# lp_basic.net
KiCad netlist of a schematic drawn in EAGLE
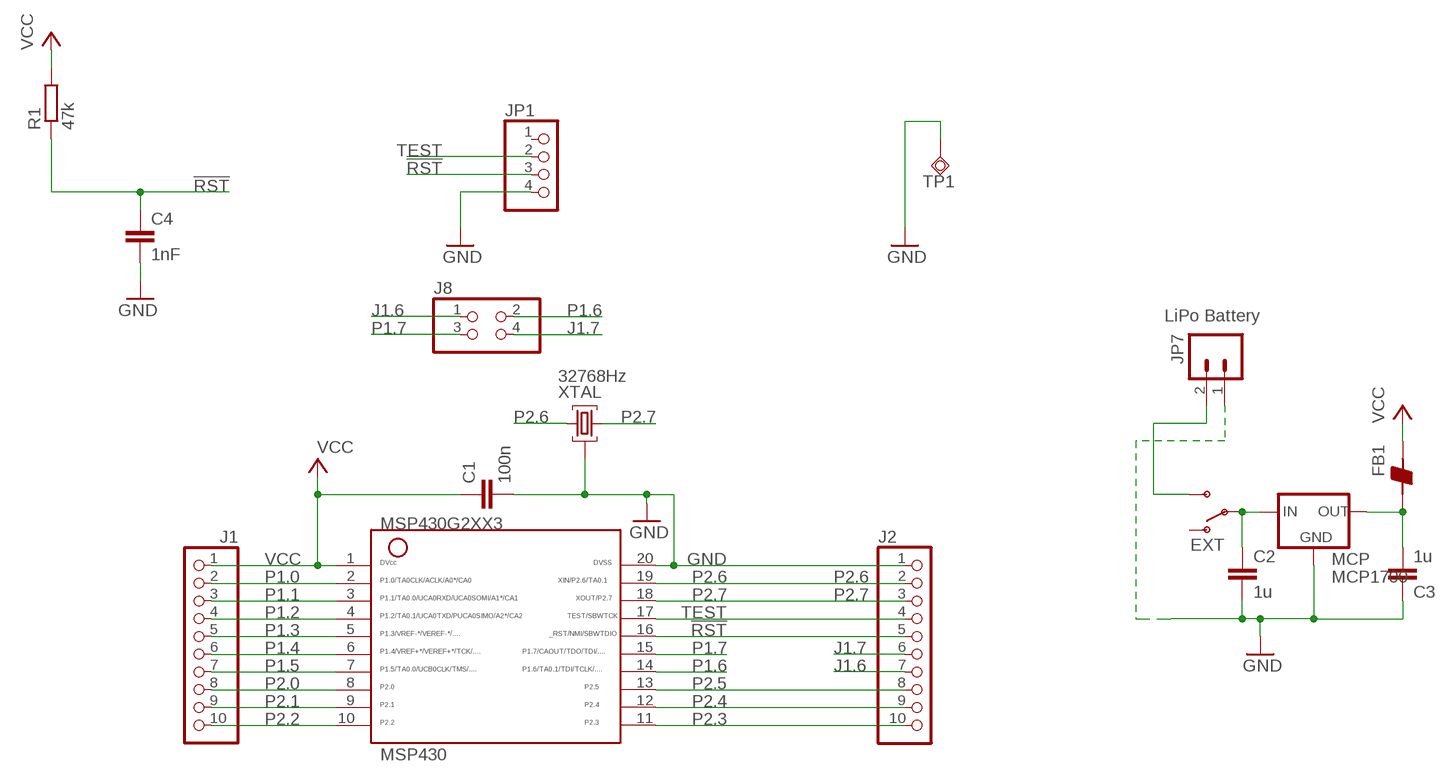
[diagram p0: schematic, sheet 1]

(export (version "E")
  (design (tool "Eeschema 10.0.6"))
  (components
    (comp (ref "C1")
      (value "100n")
      (footprint "eagle-import:C0805")
      (libsource (lib "eagle-import") (part "C-EUC0805"))
    )
    (comp (ref "C2")
      (value "1u")
      (footprint "eagle-import:C0805")
      (libsource (lib "eagle-import") (part "C-EUC0805"))
    )
    (comp (ref "C3")
      (value "1u")
      (footprint "eagle-import:C0805")
      (libsource (lib "eagle-import") (part "C-EUC0805"))
    )
    (comp (ref "C4")
      (value "1nF")
      (footprint "eagle-import:C0805")
      (libsource (lib "eagle-import") (part "resistor_C-EUC0805"))
    )
    (comp (ref "FB1")
      (value "BEAD-0805")
      (footprint "eagle-import:0805")
      (libsource (lib "eagle-import") (part "BEAD-0805"))
    )
    (comp (ref "J1")
      (value "PH1X10OCT076")
      (footprint "eagle-import:PH1X10OCT76")
      (libsource (lib "eagle-import") (part "PH1X10OCT076"))
    )
    (comp (ref "J2")
      (value "PH1X10OCT076")
      (footprint "eagle-import:PH1X10OCT76")
      (libsource (lib "eagle-import") (part "PH1X10OCT076"))
    )
    (comp (ref "J8")
      (value "PINHD-2X2")
      (footprint "eagle-import:2X02")
      (libsource (lib "eagle-import") (part "PINHD-2X2"))
    )
    (comp (ref "JP1")
      (value "PINHD-1X4")
      (footprint "eagle-import:1X04")
      (libsource (lib "eagle-import") (part "PINHD-1X4"))
    )
    (comp (ref "JP7")
      (value "LiPo Battery")
      (footprint "eagle-import:JST-2-PTH")
      (libsource (lib "eagle-import") (part "M02JST-PTH-2"))
    )
    (comp (ref "MCP")
      (value "MCP1700")
      (footprint "eagle-import:SOT-23")
      (libsource (lib "eagle-import") (part "MCP1700SOT-23"))
    )
    (comp (ref "MSP430")
      (value "MSP430N")
      (footprint "eagle-import:DIP20_HEX")
      (libsource (lib "eagle-import") (part "G2XX3---N20HEX"))
    )
    (comp (ref "ON")
      (value "EXT")
      (footprint "eagle-import:SWITCH-SPDT")
      (libsource (lib "eagle-import") (part "SWITCH-SPSTPTH"))
    )
    (comp (ref "R1")
      (value "47k")
      (footprint "eagle-import:R0805")
      (libsource (lib "eagle-import") (part "R-EU_R0805"))
    )
    (comp (ref "TP1")
      (value "TPSQTP20R")
      (footprint "eagle-import:TP20R")
      (libsource (lib "eagle-import") (part "TPSQTP20R"))
    )
    (comp (ref "XTAL")
      (value "32768Hz")
      (footprint "eagle-import:QUARZ5")
      (libsource (lib "eagle-import") (part "QUARZ5"))
    )
  )
  (nets
    (net (code "1") (name "/J1.6") (class "Default")
      (node (ref "J2") (pin "7") (pinfunction "7_7") (pintype "passive"))
      (node (ref "J8") (pin "1") (pinfunction "1_1") (pintype "passive"))
    )
    (net (code "2") (name "/J1.7") (class "Default")
      (node (ref "J2") (pin "6") (pinfunction "6_6") (pintype "passive"))
      (node (ref "J8") (pin "4") (pinfunction "4_4") (pintype "passive"))
    )
    (net (code "3") (name "/P1.0") (class "Default")
      (node (ref "J1") (pin "2") (pinfunction "2_2") (pintype "passive"))
      (node (ref "MSP430") (pin "2") (pinfunction "2_2") (pintype "bidirectional"))
    )
    (net (code "4") (name "/P1.1") (class "Default")
      (node (ref "J1") (pin "3") (pinfunction "3_3") (pintype "passive"))
      (node (ref "MSP430") (pin "3") (pinfunction "3_3") (pintype "bidirectional"))
    )
    (net (code "5") (name "/P1.2") (class "Default")
      (node (ref "J1") (pin "4") (pinfunction "4_4") (pintype "passive"))
      (node (ref "MSP430") (pin "4") (pinfunction "4_4") (pintype "bidirectional"))
    )
    (net (code "6") (name "/P1.3") (class "Default")
      (node (ref "J1") (pin "5") (pinfunction "5_5") (pintype "passive"))
      (node (ref "MSP430") (pin "5") (pinfunction "5_5") (pintype "bidirectional"))
    )
    (net (code "7") (name "/P1.4") (class "Default")
      (node (ref "J1") (pin "6") (pinfunction "6_6") (pintype "passive"))
      (node (ref "MSP430") (pin "6") (pinfunction "6_6") (pintype "bidirectional"))
    )
    (net (code "8") (name "/P1.5") (class "Default")
      (node (ref "J1") (pin "7") (pinfunction "7_7") (pintype "passive"))
      (node (ref "MSP430") (pin "7") (pinfunction "7_7") (pintype "bidirectional"))
    )
    (net (code "9") (name "/P1.6") (class "Default")
      (node (ref "J8") (pin "2") (pinfunction "2_2") (pintype "passive"))
      (node (ref "MSP430") (pin "14") (pinfunction "14_14") (pintype "bidirectional"))
    )
    (net (code "10") (name "/P1.7") (class "Default")
      (node (ref "J8") (pin "3") (pinfunction "3_3") (pintype "passive"))
      (node (ref "MSP430") (pin "15") (pinfunction "15_15") (pintype "bidirectional"))
    )
    (net (code "11") (name "/P2.0") (class "Default")
      (node (ref "J1") (pin "8") (pinfunction "8_8") (pintype "passive"))
      (node (ref "MSP430") (pin "8") (pinfunction "8_8") (pintype "bidirectional"))
    )
    (net (code "12") (name "/P2.1") (class "Default")
      (node (ref "J1") (pin "9") (pinfunction "9_9") (pintype "passive"))
      (node (ref "MSP430") (pin "9") (pinfunction "9_9") (pintype "bidirectional"))
    )
    (net (code "13") (name "/P2.2") (class "Default")
      (node (ref "J1") (pin "10") (pinfunction "10_10") (pintype "passive"))
      (node (ref "MSP430") (pin "10") (pinfunction "10_10") (pintype "bidirectional"))
    )
    (net (code "14") (name "/P2.3") (class "Default")
      (node (ref "J2") (pin "10") (pinfunction "10_10") (pintype "passive"))
      (node (ref "MSP430") (pin "11") (pinfunction "11_11") (pintype "bidirectional"))
    )
    (net (code "15") (name "/P2.4") (class "Default")
      (node (ref "J2") (pin "9") (pinfunction "9_9") (pintype "passive"))
      (node (ref "MSP430") (pin "12") (pinfunction "12_12") (pintype "bidirectional"))
    )
    (net (code "16") (name "/P2.5") (class "Default")
      (node (ref "J2") (pin "8") (pinfunction "8_8") (pintype "passive"))
      (node (ref "MSP430") (pin "13") (pinfunction "13_13") (pintype "bidirectional"))
    )
    (net (code "17") (name "/P2.6") (class "Default")
      (node (ref "J2") (pin "2") (pinfunction "2_2") (pintype "passive"))
      (node (ref "MSP430") (pin "19") (pinfunction "19_19") (pintype "bidirectional"))
      (node (ref "XTAL") (pin "2") (pinfunction "2_2") (pintype "passive"))
    )
    (net (code "18") (name "/P2.7") (class "Default")
      (node (ref "J2") (pin "3") (pinfunction "3_3") (pintype "passive"))
      (node (ref "MSP430") (pin "18") (pinfunction "18_18") (pintype "bidirectional"))
      (node (ref "XTAL") (pin "1") (pinfunction "1_1") (pintype "passive"))
    )
    (net (code "19") (name "/TEST") (class "Default")
      (node (ref "J2") (pin "4") (pinfunction "4_4") (pintype "passive"))
      (node (ref "JP1") (pin "2") (pinfunction "2_2") (pintype "passive"))
      (node (ref "MSP430") (pin "17") (pinfunction "17_17") (pintype "bidirectional"))
    )
    (net (code "20") (name "/~{RST}") (class "Default")
      (node (ref "C4") (pin "1") (pinfunction "1_1") (pintype "passive"))
      (node (ref "J2") (pin "5") (pinfunction "5_5") (pintype "passive"))
      (node (ref "JP1") (pin "3") (pinfunction "3_3") (pintype "passive"))
      (node (ref "MSP430") (pin "16") (pinfunction "16_16") (pintype "bidirectional"))
      (node (ref "R1") (pin "1") (pinfunction "1_1") (pintype "passive"))
    )
    (net (code "21") (name "GND") (class "Default")
      (node (ref "C1") (pin "2") (pinfunction "2_2") (pintype "passive"))
      (node (ref "C2") (pin "2") (pinfunction "2_2") (pintype "passive"))
      (node (ref "C3") (pin "1") (pinfunction "1_1") (pintype "passive"))
      (node (ref "C4") (pin "2") (pinfunction "2_2") (pintype "passive"))
      (node (ref "J2") (pin "1") (pinfunction "1_1") (pintype "passive"))
      (node (ref "JP1") (pin "4") (pinfunction "4_4") (pintype "passive"))
      (node (ref "JP7") (pin "1") (pinfunction "1_1") (pintype "passive"))
      (node (ref "MCP") (pin "1") (pinfunction "GND_1") (pintype "input"))
      (node (ref "MSP430") (pin "20") (pinfunction "20_20") (pintype "bidirectional"))
      (node (ref "TP1") (pin "TP") (pinfunction "TP_TP") (pintype "input"))
      (node (ref "XTAL") (pin "GND@0") (pinfunction "0_GND@0") (pintype "passive"))
    )
    (net (code "22") (name "Net-(FB1-P$1)") (class "Default")
      (node (ref "C3") (pin "2") (pinfunction "2_2") (pintype "passive"))
      (node (ref "FB1") (pin "1") (pinfunction "P$1_1") (pintype "passive"))
      (node (ref "MCP") (pin "2") (pinfunction "OUT_2") (pintype "passive"))
    )
    (net (code "23") (name "Net-(MCP-IN)") (class "Default")
      (node (ref "C2") (pin "1") (pinfunction "1_1") (pintype "passive"))
      (node (ref "MCP") (pin "3") (pinfunction "IN_3") (pintype "input"))
      (node (ref "ON") (pin "2") (pinfunction "P_2") (pintype "passive"))
    )
    (net (code "24") (name "Net-(ON-S)") (class "Default")
      (node (ref "JP7") (pin "2") (pinfunction "2_2") (pintype "passive"))
      (node (ref "ON") (pin "3") (pinfunction "S_3") (pintype "passive"))
    )
    (net (code "25") (name "VCC") (class "Default")
      (node (ref "C1") (pin "1") (pinfunction "1_1") (pintype "passive"))
      (node (ref "FB1") (pin "2") (pinfunction "P$2_2") (pintype "passive"))
      (node (ref "J1") (pin "1") (pinfunction "1_1") (pintype "passive"))
      (node (ref "MSP430") (pin "1") (pinfunction "1_1") (pintype "bidirectional"))
      (node (ref "R1") (pin "2") (pinfunction "2_2") (pintype "passive"))
    )
    (net (code "26") (name "unconnected-(JP1-Pad1)") (class "Default")
      (node (ref "JP1") (pin "1") (pinfunction "1_1") (pintype "passive"))
    )
    (net (code "27") (name "unconnected-(ON-O-Pad1)") (class "Default")
      (node (ref "ON") (pin "1") (pinfunction "O_1") (pintype "passive"))
    )
  )
)
